# DAPule-KL26Z-v1_0_0.net
KiCad netlist of a schematic drawn in EAGLE
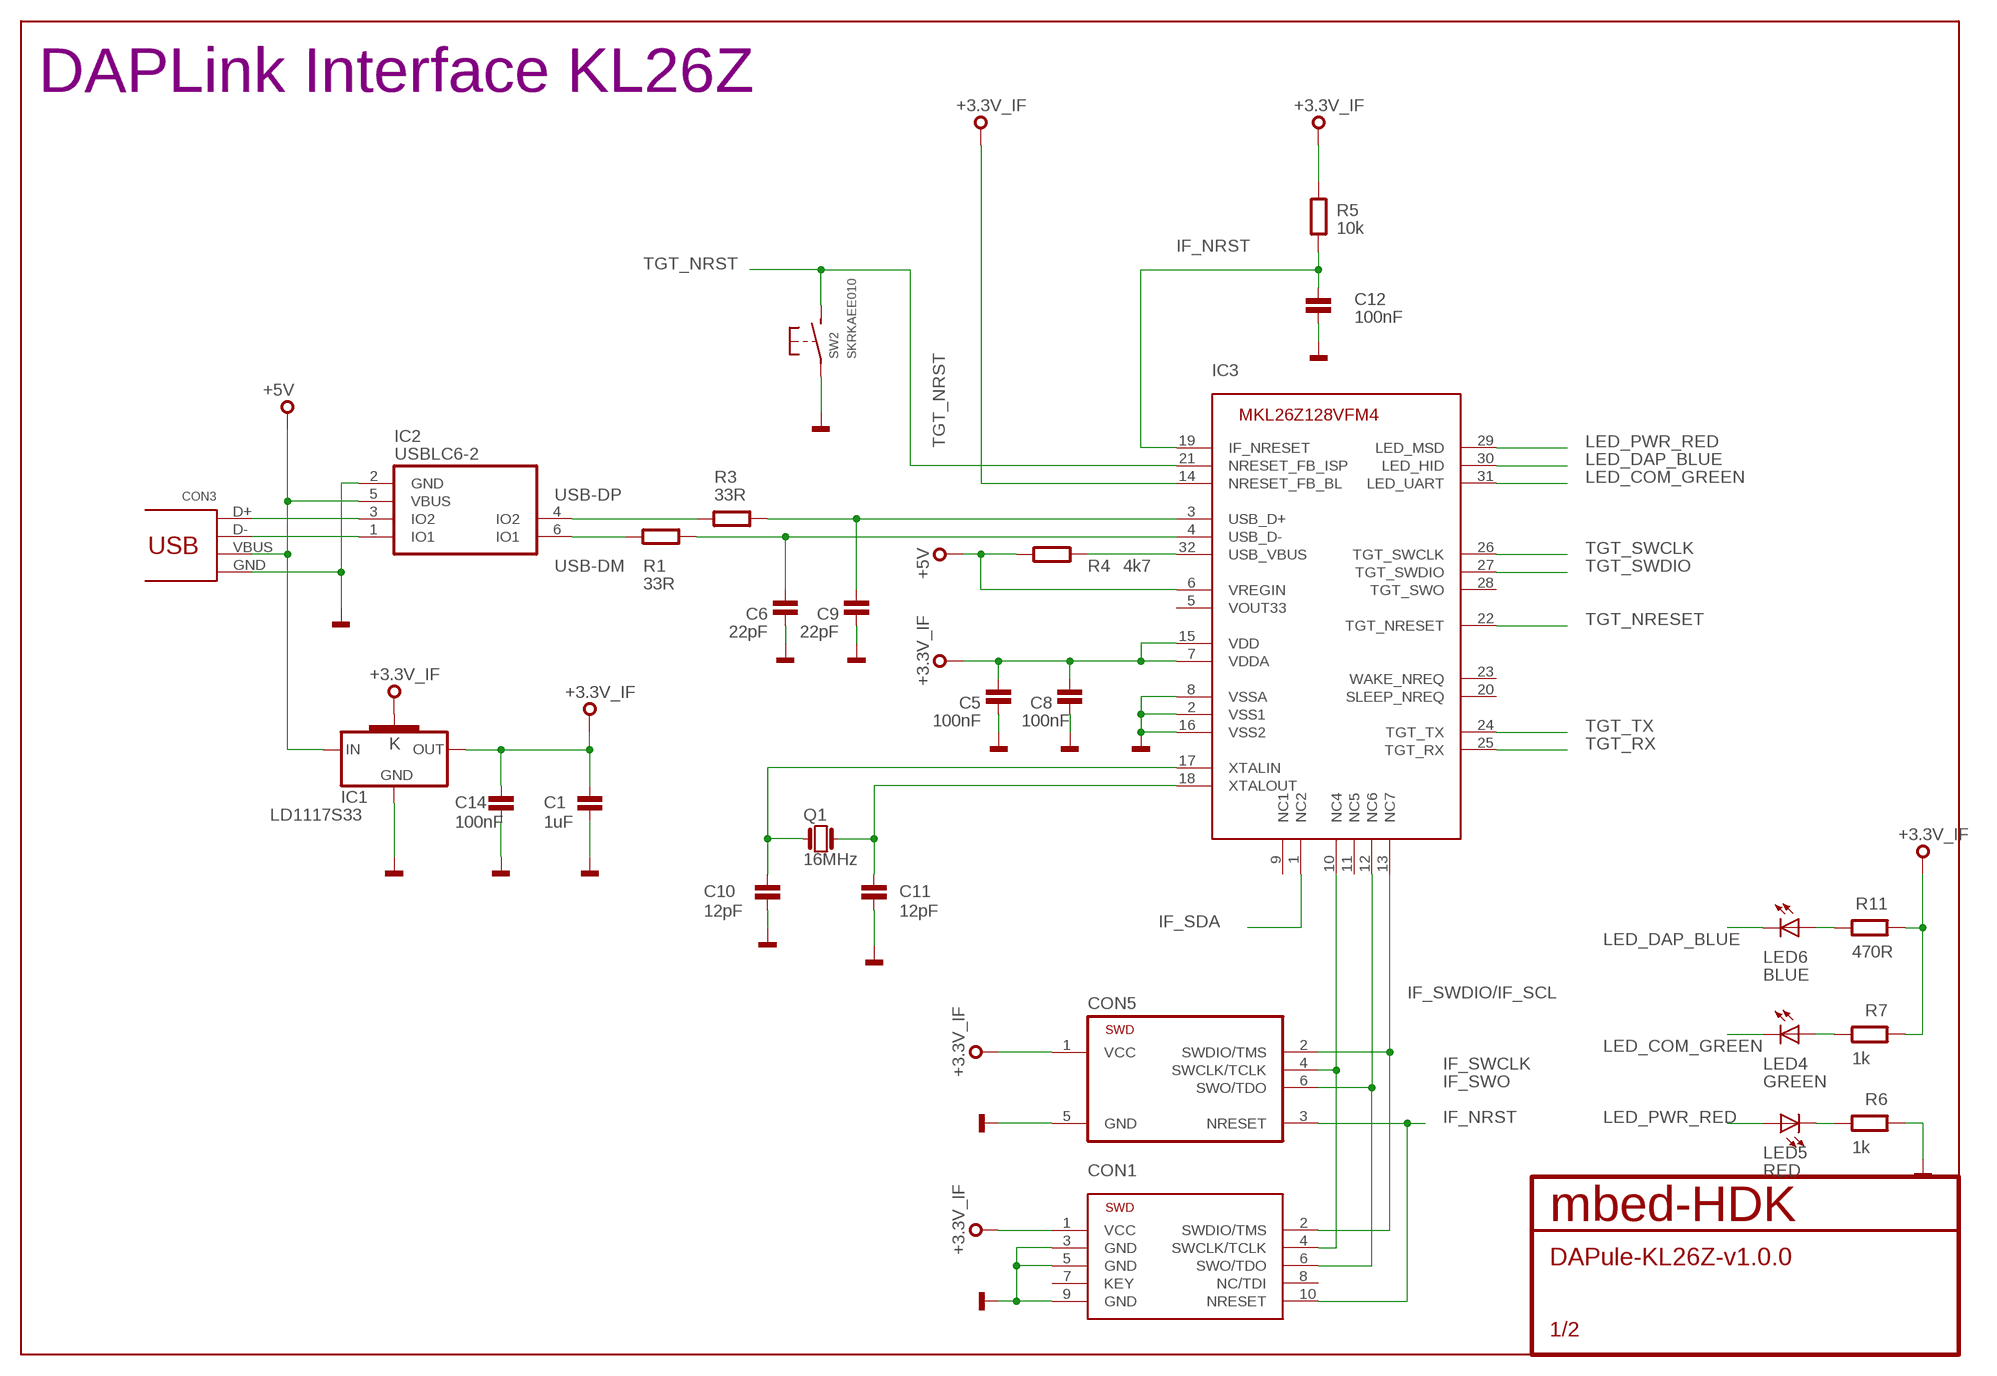
[diagram p0: schematic, sheet 1]
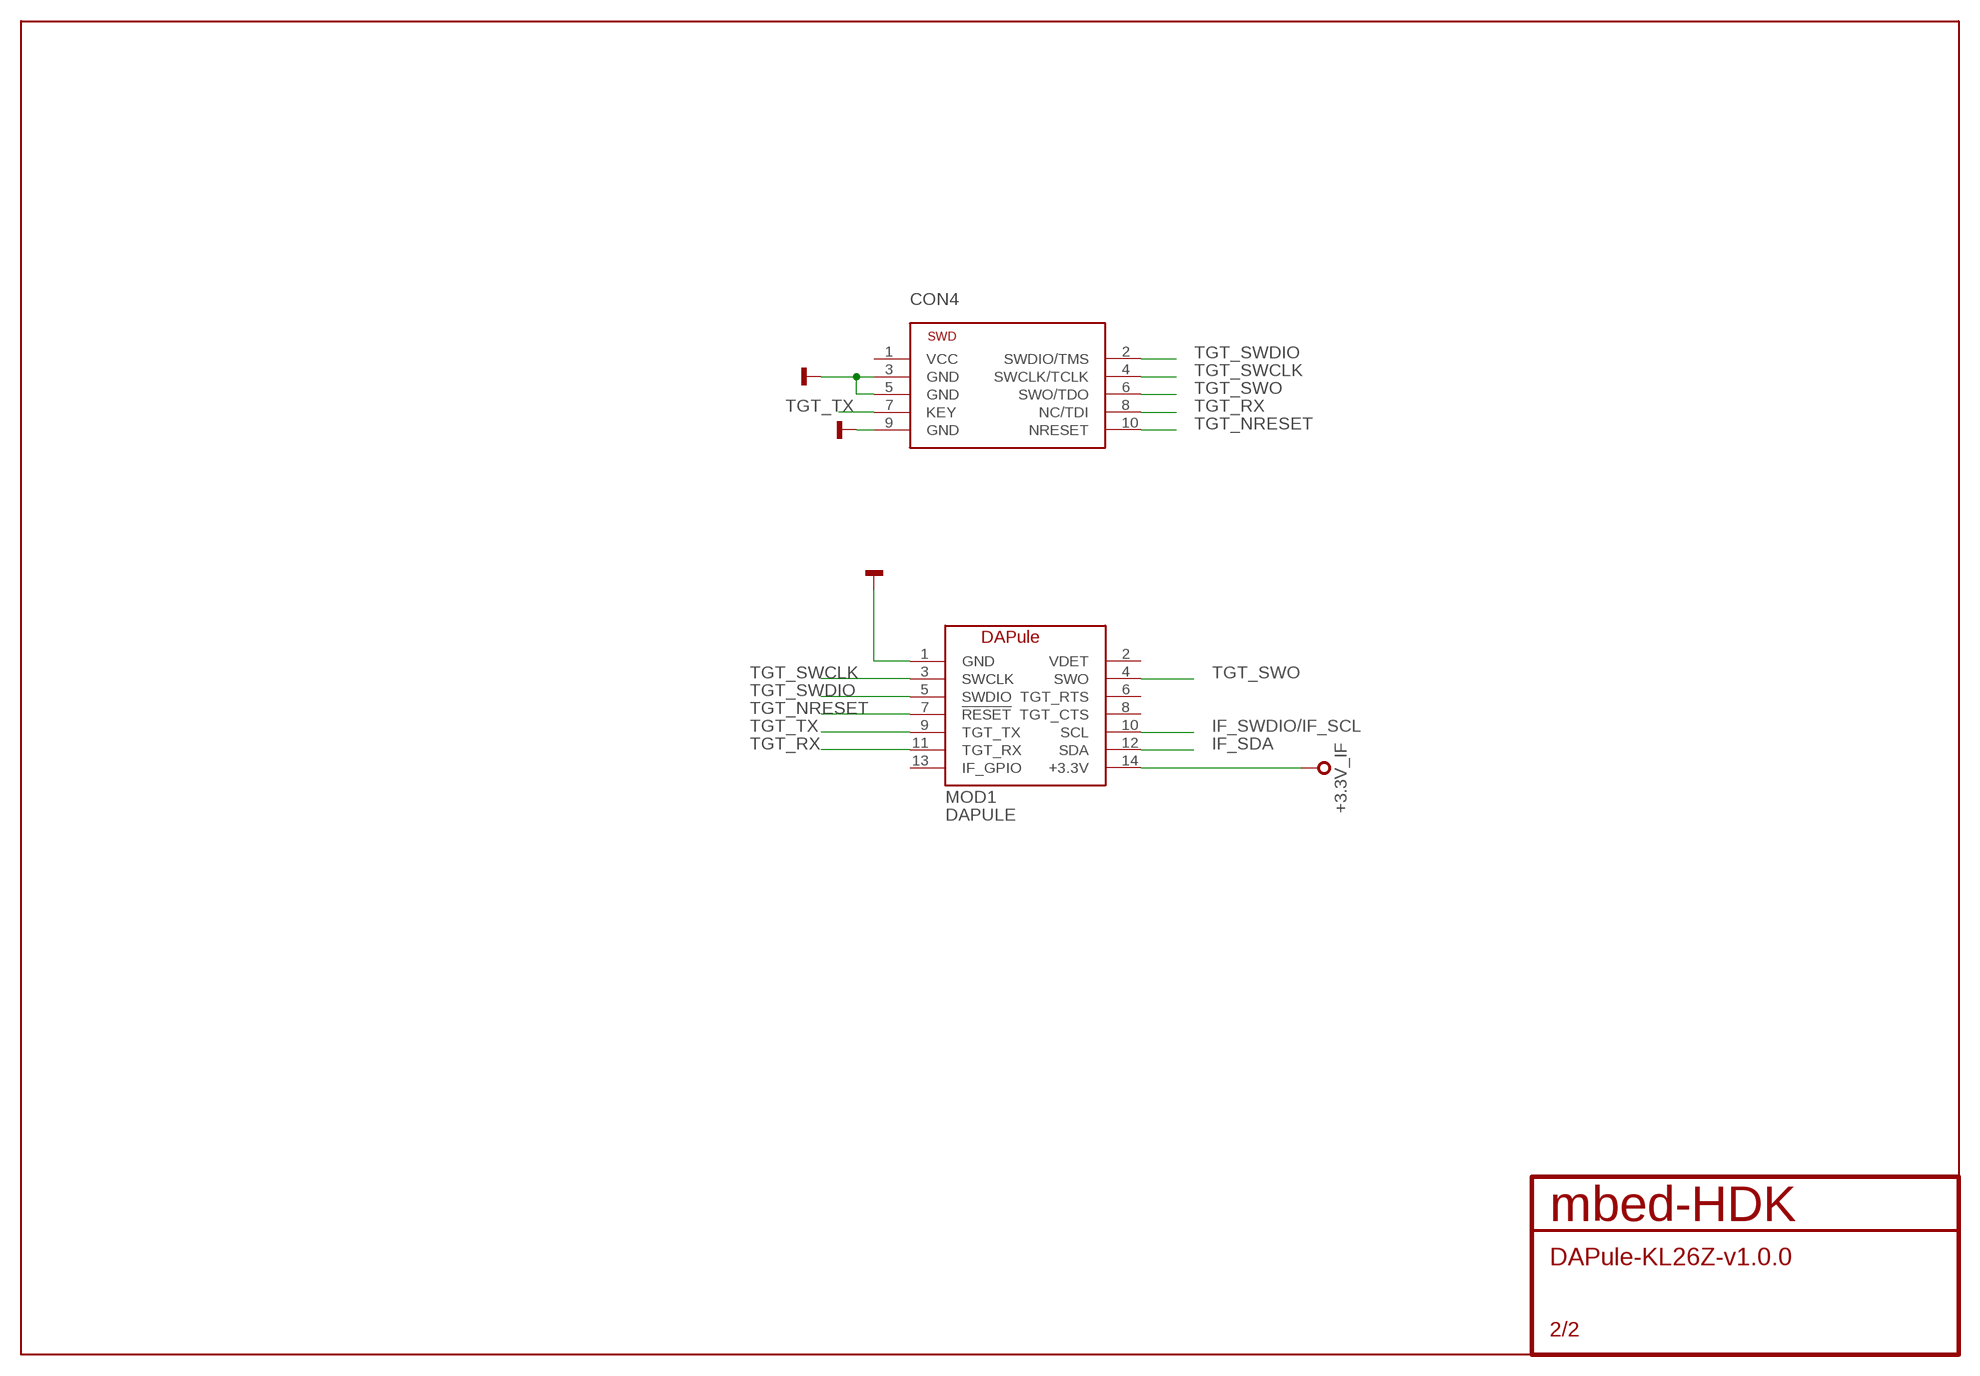
[diagram p1: schematic, sheet 2]

(export (version "E")
  (design (tool "Eeschema 10.0.6"))
  (components
    (comp (ref "CON4")
      (value "SWD-10-SMD")
      (footprint "eagle-import:SWD-10-SMD")
      (libsource (lib "eagle-import") (part "SWD-10-SMD"))
    )
    (comp (ref "MOD1")
      (value "DAPULE")
      (footprint "eagle-import:DAPULE")
      (libsource (lib "eagle-import") (part "DAPULE"))
    )
    (comp (ref "C1")
      (value "1uF")
      (footprint "eagle-import:0603")
      (libsource (lib "eagle-import") (part "C0603"))
    )
    (comp (ref "C5")
      (value "100nF")
      (footprint "eagle-import:0603")
      (libsource (lib "eagle-import") (part "C0603"))
    )
    (comp (ref "C6")
      (value "22pF")
      (footprint "eagle-import:0603")
      (libsource (lib "eagle-import") (part "C0603"))
    )
    (comp (ref "C8")
      (value "100nF")
      (footprint "eagle-import:0603")
      (libsource (lib "eagle-import") (part "C0603"))
    )
    (comp (ref "C9")
      (value "22pF")
      (footprint "eagle-import:0603")
      (libsource (lib "eagle-import") (part "C0603"))
    )
    (comp (ref "C10")
      (value "12pF")
      (footprint "eagle-import:0603")
      (libsource (lib "eagle-import") (part "C0603"))
    )
    (comp (ref "C11")
      (value "12pF")
      (footprint "eagle-import:0603")
      (libsource (lib "eagle-import") (part "C0603"))
    )
    (comp (ref "C12")
      (value "100nF")
      (footprint "eagle-import:0603")
      (libsource (lib "eagle-import") (part "C0603"))
    )
    (comp (ref "C14")
      (value "100nF")
      (footprint "eagle-import:0603")
      (libsource (lib "eagle-import") (part "C0603"))
    )
    (comp (ref "CON1")
      (value "SWD-10-SMD")
      (footprint "eagle-import:SWD-10-SMD")
      (libsource (lib "eagle-import") (part "SWD-10-SMD"))
    )
    (comp (ref "CON3")
      (value "USB_MICROB")
      (footprint "eagle-import:MOLEX-47364-0001")
      (libsource (lib "eagle-import") (part "USB_MICROB"))
    )
    (comp (ref "CON5")
      (value "TC2030-CTX-NL")
      (footprint "eagle-import:TC2030-CTX-NL")
      (libsource (lib "eagle-import") (part "TC2030-CTX-NL"))
    )
    (comp (ref "IC1")
      (value "LD1117S33")
      (footprint "eagle-import:SOT223")
      (libsource (lib "eagle-import") (part "LD1117S33"))
    )
    (comp (ref "IC2")
      (value "USBLC6-2SC6")
      (footprint "eagle-import:SOT23-6L")
      (libsource (lib "eagle-import") (part "USBLC6-2SC6"))
    )
    (comp (ref "IC3")
      (value "IF_MKL26Z128VFM4")
      (footprint "eagle-import:HVQFN32")
      (libsource (lib "eagle-import") (part "IF_MKL26Z128VFM4"))
    )
    (comp (ref "LED4")
      (value "GREEN")
      (footprint "eagle-import:CHIPLED_0603")
      (libsource (lib "eagle-import") (part "LED0603"))
    )
    (comp (ref "LED5")
      (value "RED")
      (footprint "eagle-import:CHIPLED_0603")
      (libsource (lib "eagle-import") (part "LED0603"))
    )
    (comp (ref "LED6")
      (value "BLUE")
      (footprint "eagle-import:CHIPLED_0603")
      (libsource (lib "eagle-import") (part "LED0603"))
    )
    (comp (ref "Q1")
      (value "16MHz")
      (footprint "eagle-import:2.5X2.0")
      (libsource (lib "eagle-import") (part "Q_2.5X2.0"))
    )
    (comp (ref "R1")
      (value "33R")
      (footprint "eagle-import:0603@1")
      (libsource (lib "eagle-import") (part "R0603"))
    )
    (comp (ref "R3")
      (value "33R")
      (footprint "eagle-import:0603@1")
      (libsource (lib "eagle-import") (part "R0603"))
    )
    (comp (ref "R4")
      (value "4k7")
      (footprint "eagle-import:0603@1")
      (libsource (lib "eagle-import") (part "R0603"))
    )
    (comp (ref "R5")
      (value "10k")
      (footprint "eagle-import:0603@1")
      (libsource (lib "eagle-import") (part "R0603"))
    )
    (comp (ref "R6")
      (value "1k")
      (footprint "eagle-import:0603@1")
      (libsource (lib "eagle-import") (part "R0603"))
    )
    (comp (ref "R7")
      (value "1k")
      (footprint "eagle-import:0603@1")
      (libsource (lib "eagle-import") (part "R0603"))
    )
    (comp (ref "R11")
      (value "470R")
      (footprint "eagle-import:0603@1")
      (libsource (lib "eagle-import") (part "R0603"))
    )
    (comp (ref "SW2")
      (value "SKRKAEE010")
      (footprint "eagle-import:SKRKAEE010")
      (fields (field (name "MF") "ALPS"))
      (libsource (lib "eagle-import") (part "SKRKAEE010"))
    )
  )
  (nets
    (net (code "1") (name "+3.3V_IF") (class "Default")
      (node (ref "C1") (pin "1") (pinfunction "P$1_1") (pintype "passive"))
      (node (ref "C14") (pin "1") (pinfunction "P$1_1") (pintype "passive"))
      (node (ref "C5") (pin "2") (pinfunction "P$2_2") (pintype "passive"))
      (node (ref "C8") (pin "2") (pinfunction "P$2_2") (pintype "passive"))
      (node (ref "CON1") (pin "1") (pinfunction "VCC_1") (pintype "bidirectional"))
      (node (ref "CON5") (pin "1") (pinfunction "VCC_1") (pintype "passive"))
      (node (ref "IC1") (pin "2") (pinfunction "OUT_2") (pintype "passive"))
      (node (ref "IC1") (pin "4") (pinfunction "K_4") (pintype "passive"))
      (node (ref "IC3") (pin "14") (pinfunction "NRESET_FB_BL_14") (pintype "bidirectional"))
      (node (ref "IC3") (pin "15") (pinfunction "VDD_15") (pintype "bidirectional"))
      (node (ref "IC3") (pin "7") (pinfunction "VDDA_7") (pintype "bidirectional"))
      (node (ref "MOD1") (pin "14") (pinfunction "+3.3V_14") (pintype "bidirectional"))
      (node (ref "R11") (pin "1") (pinfunction "P$1_1") (pintype "passive"))
      (node (ref "R5") (pin "2") (pinfunction "P$2_2") (pintype "passive"))
      (node (ref "R7") (pin "1") (pinfunction "P$1_1") (pintype "passive"))
    )
    (net (code "2") (name "+5V") (class "Default")
      (node (ref "CON3") (pin "VBUS") (pinfunction "VBUS_VBUS") (pintype "bidirectional"))
      (node (ref "IC1") (pin "3") (pinfunction "IN_3") (pintype "input"))
      (node (ref "IC2") (pin "5") (pinfunction "VBUS_5") (pintype "bidirectional"))
      (node (ref "IC3") (pin "6") (pinfunction "VREGIN_6") (pintype "bidirectional"))
      (node (ref "R4") (pin "1") (pinfunction "P$1_1") (pintype "passive"))
    )
    (net (code "3") (name "GND") (class "Default")
      (node (ref "C1") (pin "2") (pinfunction "P$2_2") (pintype "passive"))
      (node (ref "C10") (pin "1") (pinfunction "P$1_1") (pintype "passive"))
      (node (ref "C11") (pin "1") (pinfunction "P$1_1") (pintype "passive"))
      (node (ref "C12") (pin "1") (pinfunction "P$1_1") (pintype "passive"))
      (node (ref "C14") (pin "2") (pinfunction "P$2_2") (pintype "passive"))
      (node (ref "C5") (pin "1") (pinfunction "P$1_1") (pintype "passive"))
      (node (ref "C6") (pin "1") (pinfunction "P$1_1") (pintype "passive"))
      (node (ref "C8") (pin "1") (pinfunction "P$1_1") (pintype "passive"))
      (node (ref "C9") (pin "1") (pinfunction "P$1_1") (pintype "passive"))
      (node (ref "CON1") (pin "3") (pinfunction "GND_3") (pintype "bidirectional"))
      (node (ref "CON1") (pin "5") (pinfunction "GND_5") (pintype "bidirectional"))
      (node (ref "CON1") (pin "9") (pinfunction "GND_9") (pintype "bidirectional"))
      (node (ref "CON3") (pin "GND") (pinfunction "GND_GND") (pintype "bidirectional"))
      (node (ref "CON4") (pin "3") (pinfunction "GND_3") (pintype "bidirectional"))
      (node (ref "CON4") (pin "5") (pinfunction "GND_5") (pintype "bidirectional"))
      (node (ref "CON4") (pin "9") (pinfunction "GND_9") (pintype "bidirectional"))
      (node (ref "CON5") (pin "5") (pinfunction "GND_5") (pintype "passive"))
      (node (ref "IC1") (pin "1") (pinfunction "GND_1") (pintype "input"))
      (node (ref "IC2") (pin "2") (pinfunction "GND_2") (pintype "bidirectional"))
      (node (ref "IC3") (pin "16") (pinfunction "VSS2_16") (pintype "bidirectional"))
      (node (ref "IC3") (pin "2") (pinfunction "VSS1_2") (pintype "bidirectional"))
      (node (ref "IC3") (pin "8") (pinfunction "VSSA_8") (pintype "bidirectional"))
      (node (ref "MOD1") (pin "1") (pinfunction "GND_1") (pintype "bidirectional"))
      (node (ref "R6") (pin "1") (pinfunction "P$1_1") (pintype "passive"))
      (node (ref "SW2") (pin "P$1") (pinfunction "P_P$1") (pintype "passive"))
    )
    (net (code "4") (name "IF_NRST") (class "Default")
      (node (ref "C12") (pin "2") (pinfunction "P$2_2") (pintype "passive"))
      (node (ref "CON1") (pin "10") (pinfunction "NRESET_10") (pintype "bidirectional"))
      (node (ref "CON5") (pin "3") (pinfunction "NRESET_3") (pintype "passive"))
      (node (ref "IC3") (pin "19") (pinfunction "IF_NRESET_19") (pintype "bidirectional"))
      (node (ref "R5") (pin "1") (pinfunction "P$1_1") (pintype "passive"))
    )
    (net (code "5") (name "IF_SDA") (class "Default")
      (node (ref "IC3") (pin "1") (pinfunction "NC2_1") (pintype "bidirectional"))
      (node (ref "MOD1") (pin "12") (pinfunction "SDA_12") (pintype "bidirectional"))
    )
    (net (code "6") (name "IF_SWCLK") (class "Default")
      (node (ref "CON1") (pin "4") (pinfunction "SWCLK/TCLK_4") (pintype "bidirectional"))
      (node (ref "CON5") (pin "4") (pinfunction "SWCLK/TCLK_4") (pintype "passive"))
      (node (ref "IC3") (pin "10") (pinfunction "NC4_10") (pintype "bidirectional"))
    )
    (net (code "7") (name "IF_SWDIO{slash}IF_SCL") (class "Default")
      (node (ref "CON1") (pin "2") (pinfunction "SWDIO/TMS_2") (pintype "bidirectional"))
      (node (ref "CON5") (pin "2") (pinfunction "SWDIO/TMS_2") (pintype "passive"))
      (node (ref "IC3") (pin "13") (pinfunction "NC7_13") (pintype "bidirectional"))
      (node (ref "MOD1") (pin "10") (pinfunction "SCL_10") (pintype "bidirectional"))
    )
    (net (code "8") (name "IF_SWO") (class "Default")
      (node (ref "CON1") (pin "6") (pinfunction "SWO/TDO_6") (pintype "bidirectional"))
      (node (ref "CON5") (pin "6") (pinfunction "SWO/TDO_6") (pintype "passive"))
      (node (ref "IC3") (pin "12") (pinfunction "NC6_12") (pintype "bidirectional"))
    )
    (net (code "9") (name "LED_COM_GREEN") (class "Default")
      (node (ref "IC3") (pin "31") (pinfunction "LED_UART_31") (pintype "bidirectional"))
      (node (ref "LED4") (pin "C") (pinfunction "C_C") (pintype "passive"))
    )
    (net (code "10") (name "LED_DAP_BLUE") (class "Default")
      (node (ref "IC3") (pin "30") (pinfunction "LED_HID_30") (pintype "bidirectional"))
      (node (ref "LED6") (pin "C") (pinfunction "C_C") (pintype "passive"))
    )
    (net (code "11") (name "LED_PWR_RED") (class "Default")
      (node (ref "IC3") (pin "29") (pinfunction "LED_MSD_29") (pintype "bidirectional"))
      (node (ref "LED5") (pin "A") (pinfunction "A_A") (pintype "passive"))
    )
    (net (code "12") (name "Net-(C6-P$2)") (class "Default")
      (node (ref "C6") (pin "2") (pinfunction "P$2_2") (pintype "passive"))
      (node (ref "IC3") (pin "4") (pinfunction "USB_D-_4") (pintype "bidirectional"))
      (node (ref "R1") (pin "1") (pinfunction "P$1_1") (pintype "passive"))
    )
    (net (code "13") (name "Net-(C9-P$2)") (class "Default")
      (node (ref "C9") (pin "2") (pinfunction "P$2_2") (pintype "passive"))
      (node (ref "IC3") (pin "3") (pinfunction "USB_D+_3") (pintype "bidirectional"))
      (node (ref "R3") (pin "1") (pinfunction "P$1_1") (pintype "passive"))
    )
    (net (code "14") (name "Net-(C10-P$2)") (class "Default")
      (node (ref "C10") (pin "2") (pinfunction "P$2_2") (pintype "passive"))
      (node (ref "IC3") (pin "17") (pinfunction "XTALIN_17") (pintype "bidirectional"))
      (node (ref "Q1") (pin "1") (pinfunction "1_1") (pintype "passive"))
    )
    (net (code "15") (name "Net-(C11-P$2)") (class "Default")
      (node (ref "C11") (pin "2") (pinfunction "P$2_2") (pintype "passive"))
      (node (ref "IC3") (pin "18") (pinfunction "XTALOUT_18") (pintype "bidirectional"))
      (node (ref "Q1") (pin "3") (pinfunction "2_3") (pintype "passive"))
    )
    (net (code "16") (name "Net-(CON3-PadD+)") (class "Default")
      (node (ref "CON3") (pin "D+") (pinfunction "D+_D+") (pintype "bidirectional"))
      (node (ref "IC2") (pin "3") (pinfunction "IO2_3") (pintype "bidirectional"))
    )
    (net (code "17") (name "Net-(CON3-PadD-)") (class "Default")
      (node (ref "CON3") (pin "D-") (pinfunction "D-_D-") (pintype "bidirectional"))
      (node (ref "IC2") (pin "1") (pinfunction "IO1_1") (pintype "bidirectional"))
    )
    (net (code "18") (name "Net-(IC3-USB_VBUS)") (class "Default")
      (node (ref "IC3") (pin "32") (pinfunction "USB_VBUS_32") (pintype "bidirectional"))
      (node (ref "R4") (pin "2") (pinfunction "P$2_2") (pintype "passive"))
    )
    (net (code "19") (name "Net-(R6-P$2)") (class "Default")
      (node (ref "LED5") (pin "C") (pinfunction "C_C") (pintype "passive"))
      (node (ref "R6") (pin "2") (pinfunction "P$2_2") (pintype "passive"))
    )
    (net (code "20") (name "Net-(R7-P$2)") (class "Default")
      (node (ref "LED4") (pin "A") (pinfunction "A_A") (pintype "passive"))
      (node (ref "R7") (pin "2") (pinfunction "P$2_2") (pintype "passive"))
    )
    (net (code "21") (name "Net-(R11-P$2)") (class "Default")
      (node (ref "LED6") (pin "A") (pinfunction "A_A") (pintype "passive"))
      (node (ref "R11") (pin "2") (pinfunction "P$2_2") (pintype "passive"))
    )
    (net (code "22") (name "TGT_NRESET") (class "Default")
      (node (ref "CON4") (pin "10") (pinfunction "NRESET_10") (pintype "bidirectional"))
      (node (ref "IC3") (pin "22") (pinfunction "TGT_NRESET_22") (pintype "bidirectional"))
      (node (ref "MOD1") (pin "7") (pinfunction "~{RESET}_7") (pintype "bidirectional"))
    )
    (net (code "23") (name "TGT_NRST") (class "Default")
      (node (ref "IC3") (pin "21") (pinfunction "NRESET_FB_ISP_21") (pintype "bidirectional"))
      (node (ref "SW2") (pin "P$2") (pinfunction "S_P$2") (pintype "passive"))
    )
    (net (code "24") (name "TGT_RX") (class "Default")
      (node (ref "CON4") (pin "8") (pinfunction "NC/TDI_8") (pintype "bidirectional"))
      (node (ref "IC3") (pin "25") (pinfunction "TGT_RX_25") (pintype "bidirectional"))
      (node (ref "MOD1") (pin "11") (pinfunction "TGT_RX_11") (pintype "bidirectional"))
    )
    (net (code "25") (name "TGT_SWCLK") (class "Default")
      (node (ref "CON4") (pin "4") (pinfunction "SWCLK/TCLK_4") (pintype "bidirectional"))
      (node (ref "IC3") (pin "26") (pinfunction "TGT_SWCLK_26") (pintype "bidirectional"))
      (node (ref "MOD1") (pin "3") (pinfunction "SWCLK_3") (pintype "bidirectional"))
    )
    (net (code "26") (name "TGT_SWDIO") (class "Default")
      (node (ref "CON4") (pin "2") (pinfunction "SWDIO/TMS_2") (pintype "bidirectional"))
      (node (ref "IC3") (pin "27") (pinfunction "TGT_SWDIO_27") (pintype "bidirectional"))
      (node (ref "MOD1") (pin "5") (pinfunction "SWDIO_5") (pintype "bidirectional"))
    )
    (net (code "27") (name "TGT_SWO") (class "Default")
      (node (ref "CON4") (pin "6") (pinfunction "SWO/TDO_6") (pintype "bidirectional"))
      (node (ref "MOD1") (pin "4") (pinfunction "SWO_4") (pintype "bidirectional"))
    )
    (net (code "28") (name "TGT_TX") (class "Default")
      (node (ref "CON4") (pin "7") (pinfunction "KEY_7") (pintype "bidirectional"))
      (node (ref "IC3") (pin "24") (pinfunction "TGT_TX_24") (pintype "bidirectional"))
      (node (ref "MOD1") (pin "9") (pinfunction "TGT_TX_9") (pintype "bidirectional"))
    )
    (net (code "29") (name "USB-DM") (class "Default")
      (node (ref "IC2") (pin "6") (pinfunction "IO1_6") (pintype "bidirectional"))
      (node (ref "R1") (pin "2") (pinfunction "P$2_2") (pintype "passive"))
    )
    (net (code "30") (name "USB-DP") (class "Default")
      (node (ref "IC2") (pin "4") (pinfunction "IO2_4") (pintype "bidirectional"))
      (node (ref "R3") (pin "2") (pinfunction "P$2_2") (pintype "passive"))
    )
    (net (code "31") (name "unconnected-(CON1-KEY-Pad7)") (class "Default")
      (node (ref "CON1") (pin "7") (pinfunction "KEY_7") (pintype "bidirectional"))
    )
    (net (code "32") (name "unconnected-(CON1-NC{slash}TDI-Pad8)") (class "Default")
      (node (ref "CON1") (pin "8") (pinfunction "NC/TDI_8") (pintype "bidirectional"))
    )
    (net (code "33") (name "unconnected-(CON4-VCC-Pad1)") (class "Default")
      (node (ref "CON4") (pin "1") (pinfunction "VCC_1") (pintype "bidirectional"))
    )
    (net (code "34") (name "unconnected-(IC3-NC1-Pad9)") (class "Default")
      (node (ref "IC3") (pin "9") (pinfunction "NC1_9") (pintype "bidirectional"))
    )
    (net (code "35") (name "unconnected-(IC3-NC5-Pad11)") (class "Default")
      (node (ref "IC3") (pin "11") (pinfunction "NC5_11") (pintype "bidirectional"))
    )
    (net (code "36") (name "unconnected-(IC3-SLEEP_NREQ-Pad20)") (class "Default")
      (node (ref "IC3") (pin "20") (pinfunction "SLEEP_NREQ_20") (pintype "bidirectional"))
    )
    (net (code "37") (name "unconnected-(IC3-TGT_SWO-Pad28)") (class "Default")
      (node (ref "IC3") (pin "28") (pinfunction "TGT_SWO_28") (pintype "bidirectional"))
    )
    (net (code "38") (name "unconnected-(IC3-VOUT33-Pad5)") (class "Default")
      (node (ref "IC3") (pin "5") (pinfunction "VOUT33_5") (pintype "bidirectional"))
    )
    (net (code "39") (name "unconnected-(IC3-WAKE_NREQ-Pad23)") (class "Default")
      (node (ref "IC3") (pin "23") (pinfunction "WAKE_NREQ_23") (pintype "bidirectional"))
    )
    (net (code "40") (name "unconnected-(MOD1-IF_GPIO-Pad13)") (class "Default")
      (node (ref "MOD1") (pin "13") (pinfunction "IF_GPIO_13") (pintype "bidirectional"))
    )
    (net (code "41") (name "unconnected-(MOD1-TGT_CTS-Pad8)") (class "Default")
      (node (ref "MOD1") (pin "8") (pinfunction "TGT_CTS_8") (pintype "bidirectional"))
    )
    (net (code "42") (name "unconnected-(MOD1-TGT_RTS-Pad6)") (class "Default")
      (node (ref "MOD1") (pin "6") (pinfunction "TGT_RTS_6") (pintype "bidirectional"))
    )
    (net (code "43") (name "unconnected-(MOD1-VDET-Pad2)") (class "Default")
      (node (ref "MOD1") (pin "2") (pinfunction "VDET_2") (pintype "bidirectional"))
    )
  )
)
